# tweeq-eMod_VibMotor.net
KiCad netlist of a schematic drawn in EAGLE
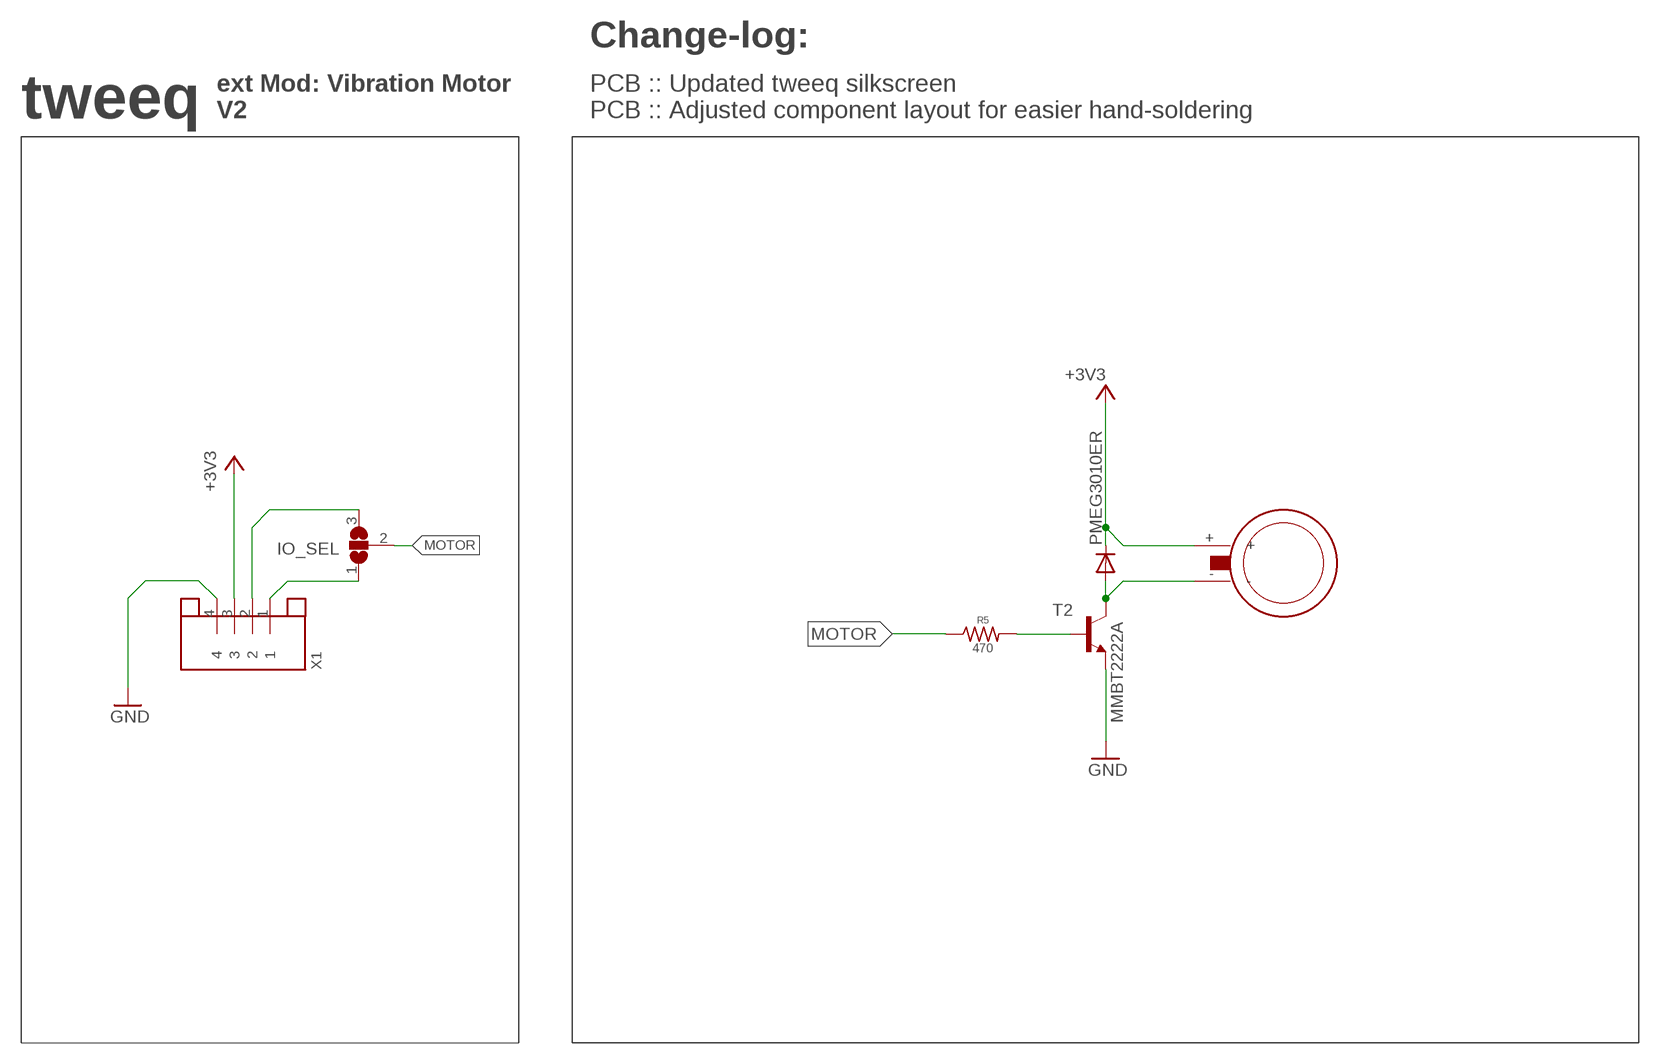
[diagram p0: schematic, sheet 1]

(export (version "E")
  (design (tool "Eeschema 10.0.6"))
  (components
    (comp (ref "IO_SEL")
      (value "JUMPER_SJ2WS")
      (footprint "eagle-import:JUMPER_SJ_S")
      (libsource (lib "eagle-import") (part "JUMPER_SJ2WS"))
    )
    (comp (ref "PMEG3010ER")
      (value "PMEG3010ER/MOD")
      (footprint "eagle-import:SOD123-MOD")
      (libsource (lib "eagle-import") (part "PMEG3010ER/MOD"))
    )
    (comp (ref "R5")
      (value "470")
      (footprint "eagle-import:R0603")
      (libsource (lib "eagle-import") (part "R-US_R0603"))
    )
    (comp (ref "T2")
      (value "2N3904MMBT3904")
      (footprint "eagle-import:SOT23-3")
      (libsource (lib "eagle-import") (part "2N3904MMBT3904"))
    )
    (comp (ref "U$2")
      (value "VMOTOR_10")
      (footprint "eagle-import:VMOTOR_10")
      (libsource (lib "eagle-import") (part "VMOTOR_10"))
    )
    (comp (ref "X1")
      (value "JST-4PINSH")
      (footprint "eagle-import:SH1.0-4PIN")
      (libsource (lib "eagle-import") (part "JST-4PINSH"))
    )
  )
  (nets
    (net (code "1") (name "+3V3") (class "Default")
      (node (ref "PMEG3010ER") (pin "C") (pinfunction "C_C") (pintype "passive"))
      (node (ref "U$2") (pin "+") (pinfunction "+_+") (pintype "power_in"))
      (node (ref "X1") (pin "3") (pinfunction "3_3") (pintype "bidirectional"))
    )
    (net (code "2") (name "GND") (class "Default")
      (node (ref "T2") (pin "2") (pinfunction "E_2") (pintype "passive"))
      (node (ref "X1") (pin "4") (pinfunction "4_4") (pintype "bidirectional"))
    )
    (net (code "3") (name "MOTOR") (class "Default")
      (node (ref "IO_SEL") (pin "2") (pinfunction "2_2") (pintype "passive"))
      (node (ref "R5") (pin "1") (pinfunction "1_1") (pintype "passive"))
    )
    (net (code "4") (name "Net-(IO_SEL-Pad1)") (class "Default")
      (node (ref "IO_SEL") (pin "1") (pinfunction "1_1") (pintype "passive"))
      (node (ref "X1") (pin "1") (pinfunction "1_1") (pintype "bidirectional"))
    )
    (net (code "5") (name "Net-(IO_SEL-Pad3)") (class "Default")
      (node (ref "IO_SEL") (pin "3") (pinfunction "3_3") (pintype "passive"))
      (node (ref "X1") (pin "2") (pinfunction "2_2") (pintype "bidirectional"))
    )
    (net (code "6") (name "Net-(T2-B)") (class "Default")
      (node (ref "R5") (pin "2") (pinfunction "2_2") (pintype "passive"))
      (node (ref "T2") (pin "1") (pinfunction "B_1") (pintype "passive"))
    )
    (net (code "7") (name "Net-(T2-C)") (class "Default")
      (node (ref "PMEG3010ER") (pin "A") (pinfunction "A_A") (pintype "passive"))
      (node (ref "T2") (pin "3") (pinfunction "C_3") (pintype "passive"))
      (node (ref "U$2") (pin "-") (pinfunction "-_-") (pintype "power_in"))
    )
  )
)
